# Encoder.net
KiCad netlist of a schematic drawn in Altium Designer
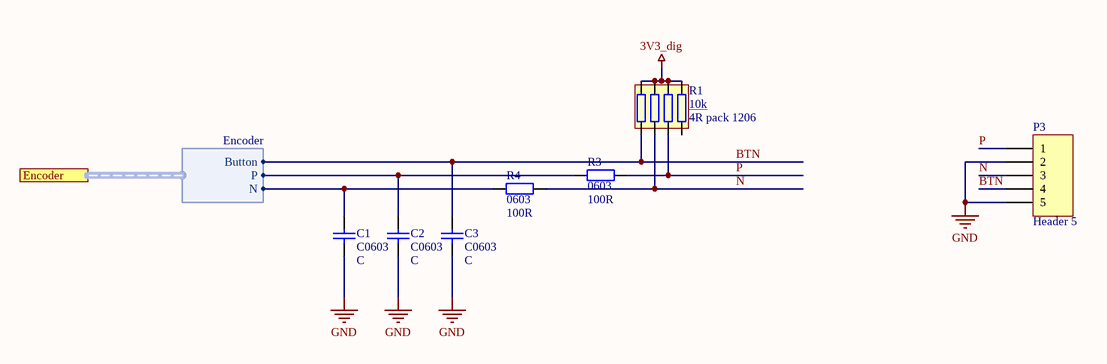
[diagram p0: Encoder.SchDoc]

(export (version "E")
  (design (tool "Eeschema 10.0.6"))
  (components
    (comp (ref "C1")
      (value "C")
      (footprint "C0603")
      (description "Generic capacitor")
      (libsource (lib "_RLC") (part "Cap"))
    )
    (comp (ref "C2")
      (value "C")
      (footprint "C0603")
      (description "Generic capacitor")
      (libsource (lib "_RLC") (part "Cap"))
    )
    (comp (ref "C3")
      (value "C")
      (footprint "C0603")
      (description "Generic capacitor")
      (libsource (lib "_RLC") (part "Cap"))
    )
    (comp (ref "P3")
      (value "Header 5")
      (footprint "HDR1X5")
      (description "Header, 5-Pin")
      (fields (field (name "PUBLISHER") "Altium Limited"))
      (libsource (lib "_Connectors") (part "Header 5"))
    )
    (comp (ref "R1")
      (value "10k")
      (footprint "4R pack 1206")
      (description "4 resistor pack array")
      (libsource (lib "_RLC") (part "Rres_pack_4"))
    )
    (comp (ref "R3")
      (value "100R")
      (footprint "0603")
      (description "Generic resistor")
      (libsource (lib "_RLC") (part "Res"))
    )
    (comp (ref "R4")
      (value "100R")
      (footprint "0603")
      (description "Generic resistor")
      (libsource (lib "_RLC") (part "Res"))
    )
  )
  (nets
    (net (code "2") (name "/BTN") (class "Default")
      (node (ref "C3") (pin "1") (pinfunction "1_1") (pintype "passive"))
      (node (ref "P3") (pin "4") (pinfunction "4_4") (pintype "passive"))
      (node (ref "R1") (pin "4") (pinfunction "4_4") (pintype "passive"))
    )
    (net (code "3") (name "/N") (class "Default")
      (node (ref "P3") (pin "3") (pinfunction "3_3") (pintype "passive"))
      (node (ref "R1") (pin "3") (pinfunction "3_3") (pintype "passive"))
      (node (ref "R4") (pin "2") (pinfunction "2_2") (pintype "passive"))
    )
    (net (code "4") (name "/P") (class "Default")
      (node (ref "P3") (pin "1") (pinfunction "1_1") (pintype "passive"))
      (node (ref "R1") (pin "2") (pinfunction "2_2") (pintype "passive"))
      (node (ref "R3") (pin "2") (pinfunction "2_2") (pintype "passive"))
    )
    (net (code "6") (name "3V3_dig") (class "Default")
      (node (ref "R1") (pin "5") (pinfunction "5_5") (pintype "passive"))
      (node (ref "R1") (pin "6") (pinfunction "6_6") (pintype "passive"))
      (node (ref "R1") (pin "7") (pinfunction "7_7") (pintype "passive"))
      (node (ref "R1") (pin "8") (pinfunction "8_8") (pintype "passive"))
    )
    (net (code "7") (name "GND") (class "Default")
      (node (ref "C1") (pin "2") (pinfunction "2_2") (pintype "passive"))
      (node (ref "C2") (pin "2") (pinfunction "2_2") (pintype "passive"))
      (node (ref "C3") (pin "2") (pinfunction "2_2") (pintype "passive"))
      (node (ref "P3") (pin "2") (pinfunction "2_2") (pintype "passive"))
      (node (ref "P3") (pin "5") (pinfunction "5_5") (pintype "passive"))
    )
    (net (code "8") (name "Net-(C1-Pad1)") (class "Default")
      (node (ref "C1") (pin "1") (pinfunction "1_1") (pintype "passive"))
      (node (ref "R4") (pin "1") (pinfunction "1_1") (pintype "passive"))
    )
    (net (code "9") (name "Net-(C2-Pad1)") (class "Default")
      (node (ref "C2") (pin "1") (pinfunction "1_1") (pintype "passive"))
      (node (ref "R3") (pin "1") (pinfunction "1_1") (pintype "passive"))
    )
    (net (code "10") (name "unconnected-(R1-Pad1)") (class "Default")
      (node (ref "R1") (pin "1") (pinfunction "1_1") (pintype "passive"))
    )
  )
)
